# LT3094.net
KiCad netlist of a schematic drawn in Altium Designer
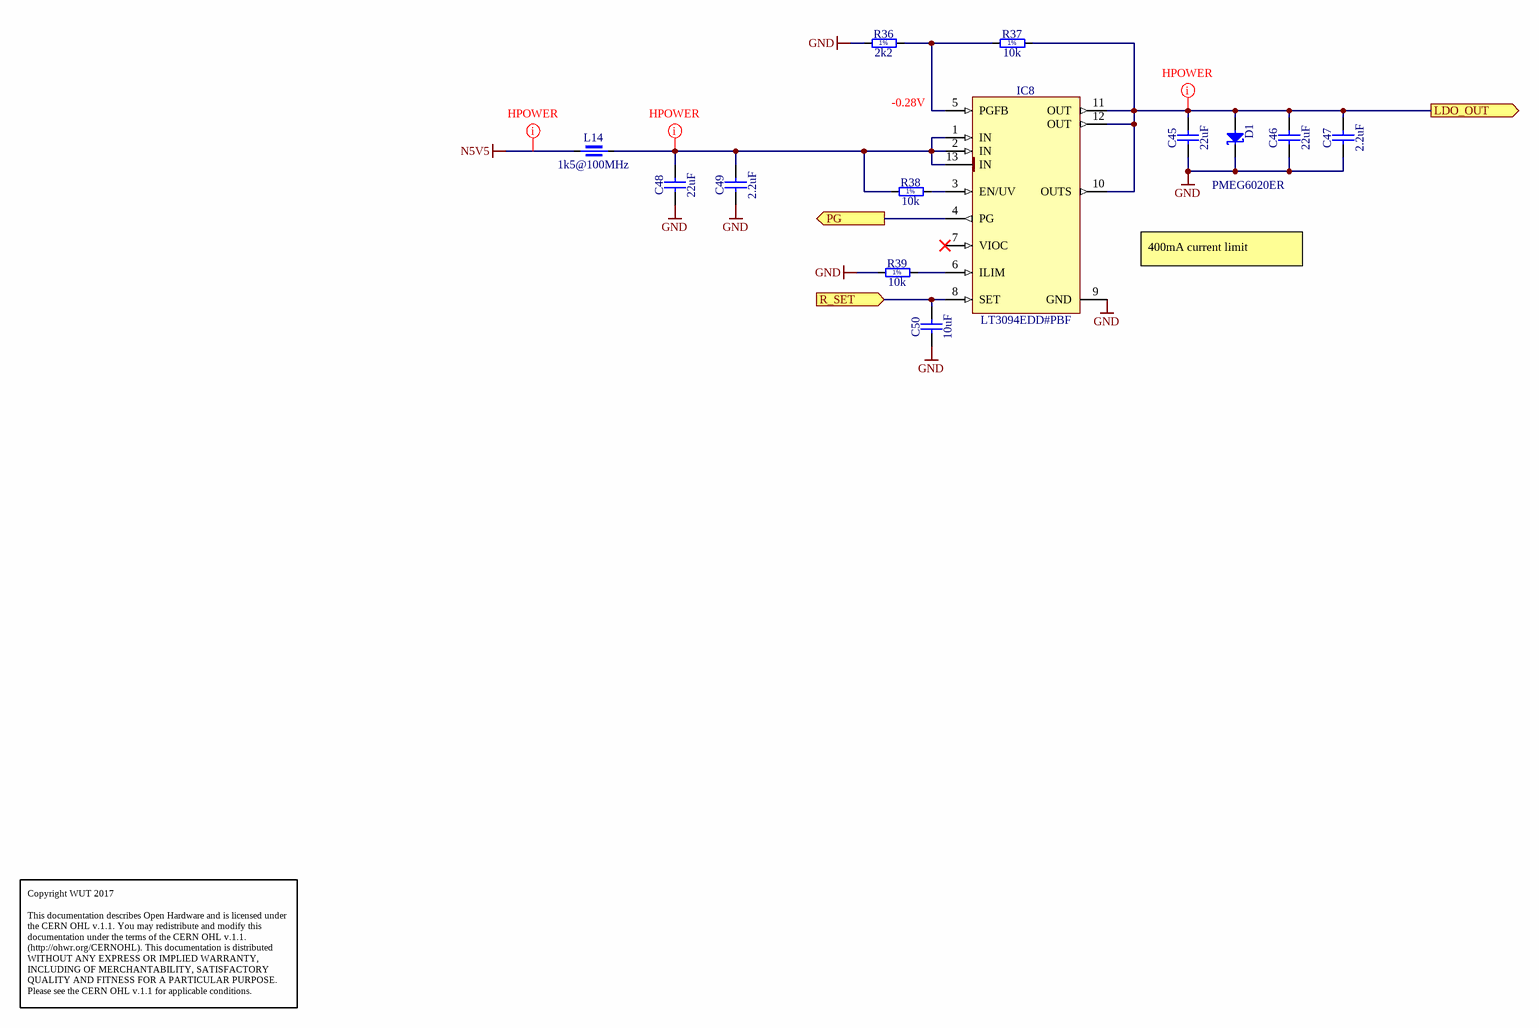
[diagram p0: LT3094.SchDoc]

(export (version "E")
  (design (tool "Eeschema 10.0.6"))
  (components
    (comp (ref "C45")
      (value "22uF")
      (footprint "CAPC3225X140N")
      (description "Non-polarised capacitor")
      (fields
        (field (name "PART NUMBER") "CC1210_22UF_25V_20%_X7R")
        (field (name "VOLTAGE") "25V")
        (field (name "AUTHOR") "CERN DEM JLC")
      )
      (libsource (lib "Capacitors") (part "Capacitor - non polarized"))
    )
    (comp (ref "C46")
      (value "22uF")
      (footprint "CAPC3225X140N")
      (description "Non-polarised capacitor")
      (fields
        (field (name "PART NUMBER") "CC1210_22UF_25V_20%_X7R")
        (field (name "VOLTAGE") "25V")
        (field (name "AUTHOR") "CERN DEM JLC")
      )
      (libsource (lib "Capacitors") (part "Capacitor - non polarized"))
    )
    (comp (ref "C47")
      (value "2.2uF")
      (footprint "CAPC1608X87N")
      (description "Non-polarised capacitor")
      (fields
        (field (name "PART NUMBER") "CC0603_2.2UF_16V_10%_X5R")
        (field (name "VOLTAGE") "16V")
        (field (name "AUTHOR") "CERN DEM JLC")
      )
      (libsource (lib "Capacitors") (part "Capacitor - non polarized"))
    )
    (comp (ref "C48")
      (value "22uF")
      (footprint "CAPC3225X140N")
      (description "Non-polarised capacitor")
      (fields
        (field (name "PART NUMBER") "CC1210_22UF_25V_20%_X7R")
        (field (name "VOLTAGE") "25V")
        (field (name "AUTHOR") "CERN DEM JLC")
      )
      (libsource (lib "Capacitors") (part "Capacitor - non polarized"))
    )
    (comp (ref "C49")
      (value "2.2uF")
      (footprint "CAPC1608X87N")
      (description "Non-polarised capacitor")
      (fields
        (field (name "PART NUMBER") "CC0603_2.2UF_16V_10%_X5R")
        (field (name "VOLTAGE") "16V")
        (field (name "AUTHOR") "CERN DEM JLC")
      )
      (libsource (lib "Capacitors") (part "Capacitor - non polarized"))
    )
    (comp (ref "C50")
      (value "10uF")
      (footprint "CAPC2012X135N")
      (description "Non-polarised capacitor")
      (fields
        (field (name "PART NUMBER") "CC0805_10UF_10V_10%_X7R")
        (field (name "VOLTAGE") "10V")
        (field (name "AUTHOR") "CERN DEM JLC")
      )
      (libsource (lib "Capacitors") (part "Capacitor - non polarized"))
    )
    (comp (ref "D1")
      (value "PMEG6020ER")
      (footprint "SODFL3517X110N")
      (description "Schottky Diode")
      (fields
        (field (name "VOLTAGE") "60V")
        (field (name "POWER") "2A")
        (field (name "AUTHOR") "CERN DEM JMW")
      )
      (libsource (lib "ICs And Semiconductors") (part "Diode Schottky"))
    )
    (comp (ref "IC8")
      (value "LT3094EDD#PBF")
      (footprint "SON45P300X300X80-13N-R175X248")
      (description "-20V, 500mA, Ultralow Noise, Ultrahigh PSRR Negative Linear Regulator")
      (fields (field (name "MANUFACTURER") "LINEAR TECHNOLOGY") (field (name "AUTHOR") "CERN DEM JLC"))
      (libsource (lib "ICs And Semiconductors") (part "LT3094"))
    )
    (comp (ref "L14")
      (value "1k5@100MHz")
      (footprint "INDC2012X110N")
      (fields
        (field (name "PART NUMBER") "IND0805_WURTH_742792097")
        (field (name "POWER") "1A")
        (field (name "TOLERANCE") "±25%")
        (field (name "AUTHOR") "CERN DEM MR")
      )
      (libsource (lib "Inductors & Transformers") (part "Ferrite Bead"))
    )
    (comp (ref "R36")
      (value "2k2")
      (footprint "RESC1005X40N")
      (description "Resistor - 1%")
      (fields
        (field (name "PART NUMBER") "R0402_2K2_1%_0.0625W_100PPM")
        (field (name "POWER") "0.0625W")
        (field (name "AUTHOR") "CERN DEM JLC")
      )
      (libsource (lib "Resistors") (part "Resistor - 1%"))
    )
    (comp (ref "R37")
      (value "10k")
      (footprint "RESC1005X40N")
      (description "Resistor - 1%")
      (fields
        (field (name "PART NUMBER") "R0402_10K_1%_0.0625W_100PPM")
        (field (name "POWER") "0.0625W")
        (field (name "AUTHOR") "CERN DEM JLC")
      )
      (libsource (lib "Resistors") (part "Resistor - 1%"))
    )
    (comp (ref "R38")
      (value "10k")
      (footprint "RESC1005X40N")
      (description "Resistor - 1%")
      (fields
        (field (name "PART NUMBER") "R0402_10K_1%_0.0625W_100PPM")
        (field (name "POWER") "0.0625W")
        (field (name "AUTHOR") "CERN DEM JLC")
      )
      (libsource (lib "Resistors") (part "Resistor - 1%"))
    )
    (comp (ref "R39")
      (value "10k")
      (footprint "RESC1005X40N")
      (description "Resistor - 1%")
      (fields
        (field (name "PART NUMBER") "R0402_10K_1%_0.0625W_100PPM")
        (field (name "POWER") "0.0625W")
        (field (name "AUTHOR") "CERN DEM JLC")
      )
      (libsource (lib "Resistors") (part "Resistor - 1%"))
    )
  )
  (nets
    (net (code "1") (name "/LDO_OUT") (class "Default")
      (node (ref "C45") (pin "2") (pinfunction "2_2") (pintype "passive"))
      (node (ref "C46") (pin "2") (pinfunction "2_2") (pintype "passive"))
      (node (ref "C47") (pin "2") (pinfunction "2_2") (pintype "passive"))
      (node (ref "D1") (pin "2") (pinfunction "A_2") (pintype "passive"))
      (node (ref "IC8") (pin "10") (pinfunction "OUTS_10") (pintype "output"))
      (node (ref "IC8") (pin "11") (pinfunction "OUT_11") (pintype "output"))
      (node (ref "IC8") (pin "12") (pinfunction "OUT_12") (pintype "output"))
      (node (ref "R37") (pin "2") (pinfunction "2_2") (pintype "passive"))
    )
    (net (code "2") (name "/PG") (class "Default")
      (node (ref "IC8") (pin "4") (pinfunction "PG_4") (pintype "output"))
    )
    (net (code "3") (name "/R_SET") (class "Default")
      (node (ref "C50") (pin "2") (pinfunction "2_2") (pintype "passive"))
      (node (ref "IC8") (pin "8") (pinfunction "SET_8") (pintype "input"))
    )
    (net (code "4") (name "GND") (class "Default")
      (node (ref "C45") (pin "1") (pinfunction "1_1") (pintype "passive"))
      (node (ref "C46") (pin "1") (pinfunction "1_1") (pintype "passive"))
      (node (ref "C47") (pin "1") (pinfunction "1_1") (pintype "passive"))
      (node (ref "C48") (pin "1") (pinfunction "1_1") (pintype "passive"))
      (node (ref "C49") (pin "1") (pinfunction "1_1") (pintype "passive"))
      (node (ref "C50") (pin "1") (pinfunction "1_1") (pintype "passive"))
      (node (ref "D1") (pin "1") (pinfunction "C_1") (pintype "passive"))
      (node (ref "IC8") (pin "9") (pinfunction "GND_9") (pintype "power_in"))
      (node (ref "R36") (pin "1") (pinfunction "1_1") (pintype "passive"))
      (node (ref "R39") (pin "1") (pinfunction "1_1") (pintype "passive"))
    )
    (net (code "5") (name "N5V5") (class "Default")
      (node (ref "L14") (pin "1") (pinfunction "1_1") (pintype "passive"))
    )
    (net (code "6") (name "Net-(C48-Pad2)") (class "Default")
      (node (ref "C48") (pin "2") (pinfunction "2_2") (pintype "passive"))
      (node (ref "C49") (pin "2") (pinfunction "2_2") (pintype "passive"))
      (node (ref "IC8") (pin "1") (pinfunction "IN_1") (pintype "input"))
      (node (ref "IC8") (pin "13") (pinfunction "IN_13") (pintype "power_in"))
      (node (ref "IC8") (pin "2") (pinfunction "IN_2") (pintype "input"))
      (node (ref "L14") (pin "2") (pinfunction "2_2") (pintype "passive"))
      (node (ref "R38") (pin "1") (pinfunction "1_1") (pintype "passive"))
    )
    (net (code "7") (name "Net-(IC8-EN{slash}UV)") (class "Default")
      (node (ref "IC8") (pin "3") (pinfunction "EN/UV_3") (pintype "input"))
      (node (ref "R38") (pin "2") (pinfunction "2_2") (pintype "passive"))
    )
    (net (code "8") (name "Net-(IC8-ILIM)") (class "Default")
      (node (ref "IC8") (pin "6") (pinfunction "ILIM_6") (pintype "input"))
      (node (ref "R39") (pin "2") (pinfunction "2_2") (pintype "passive"))
    )
    (net (code "9") (name "Net-(IC8-PGFB)") (class "Default")
      (node (ref "IC8") (pin "5") (pinfunction "PGFB_5") (pintype "input"))
      (node (ref "R36") (pin "2") (pinfunction "2_2") (pintype "passive"))
      (node (ref "R37") (pin "1") (pinfunction "1_1") (pintype "passive"))
    )
    (net (code "10") (name "unconnected-(IC8-VIOC-Pad7)") (class "Default")
      (node (ref "IC8") (pin "7") (pinfunction "VIOC_7") (pintype "input+no_connect"))
    )
  )
)
